# LH__MRF24_Module.net
KiCad netlist of a schematic drawn in EAGLE
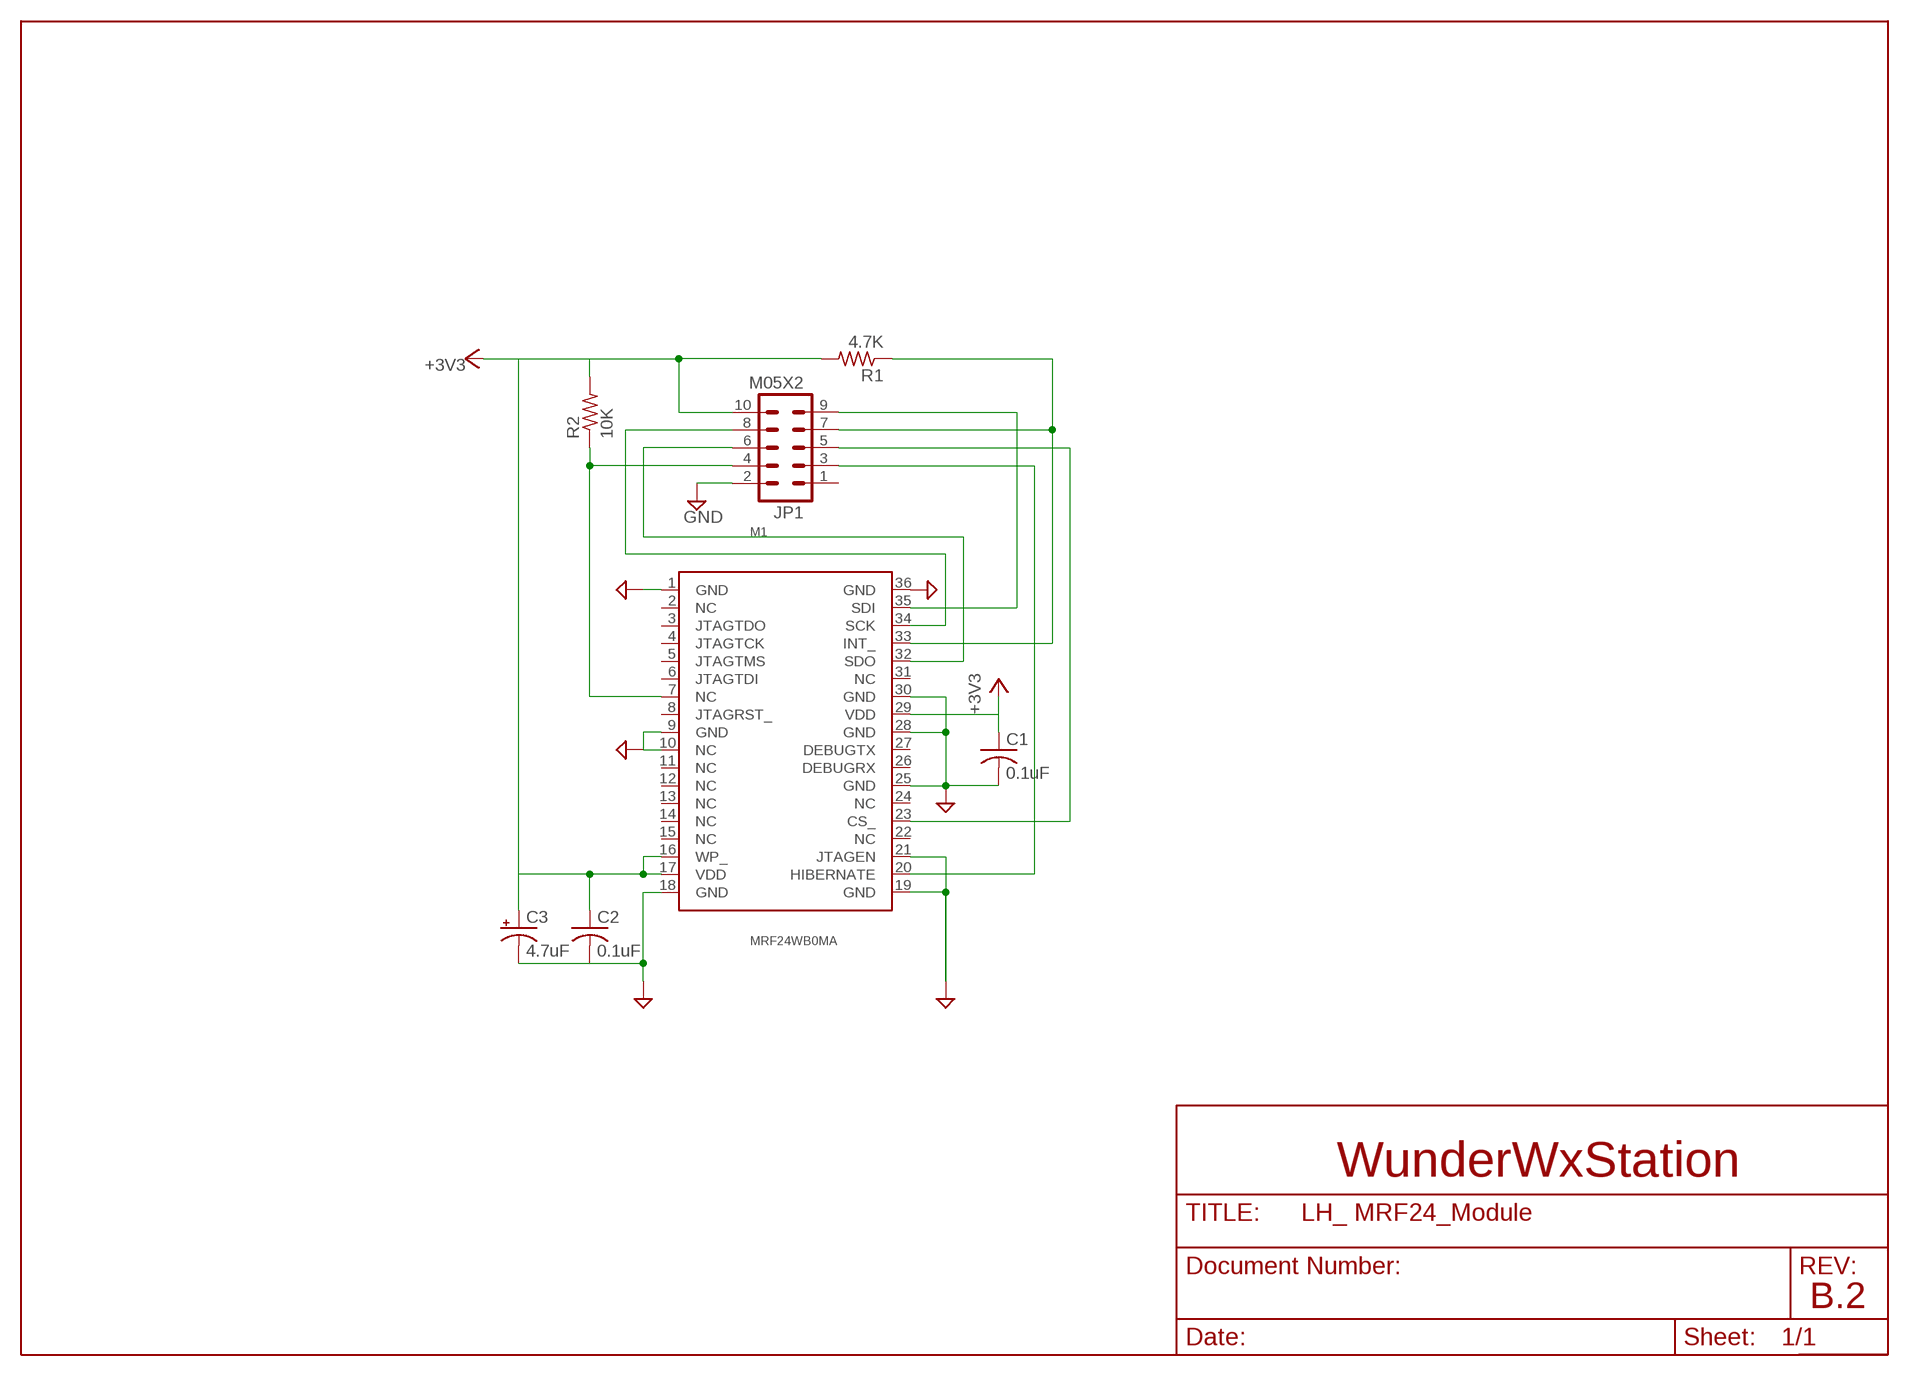
[diagram p0: schematic, sheet 1]

(export (version "E")
  (design (tool "Eeschema 10.0.6"))
  (components
    (comp (ref "C1")
      (value "0.1uF")
      (footprint "eagle-import:C0805")
      (libsource (lib "eagle-import") (part "C-USC0805"))
    )
    (comp (ref "C2")
      (value "0.1uF")
      (footprint "eagle-import:C0805")
      (libsource (lib "eagle-import") (part "C-USC0805"))
    )
    (comp (ref "C3")
      (value "4.7uF")
      (footprint "eagle-import:R_2012-12R")
      (libsource (lib "eagle-import") (part "CPOL-USR/2012-12R"))
    )
    (comp (ref "JP1")
      (value "M05X2")
      (footprint "eagle-import:2X5-RA-HEADER")
      (libsource (lib "eagle-import") (part "M05X2"))
    )
    (comp (ref "M1")
      (value "MRF24WB0MA")
      (footprint "eagle-import:MRF24W")
      (libsource (lib "eagle-import") (part "MR24WB0MA"))
    )
    (comp (ref "R1")
      (value "4.7K")
      (footprint "eagle-import:R0603")
      (libsource (lib "eagle-import") (part "R-US_R0603"))
    )
    (comp (ref "R2")
      (value "10K")
      (footprint "eagle-import:R0603")
      (libsource (lib "eagle-import") (part "R-US_R0603"))
    )
  )
  (nets
    (net (code "1") (name "+3V3") (class "Default")
      (node (ref "C1") (pin "1") (pinfunction "1_1") (pintype "passive"))
      (node (ref "C2") (pin "1") (pinfunction "1_1") (pintype "passive"))
      (node (ref "C3") (pin "+") (pinfunction "+_+") (pintype "passive"))
      (node (ref "JP1") (pin "10") (pinfunction "10_10") (pintype "passive"))
      (node (ref "M1") (pin "16") (pinfunction "WP__16") (pintype "bidirectional"))
      (node (ref "M1") (pin "17") (pinfunction "VDD_17") (pintype "bidirectional"))
      (node (ref "M1") (pin "29") (pinfunction "VDD_29") (pintype "bidirectional"))
      (node (ref "R1") (pin "2") (pinfunction "2_2") (pintype "passive"))
      (node (ref "R2") (pin "2") (pinfunction "2_2") (pintype "passive"))
    )
    (net (code "2") (name "GND") (class "Default")
      (node (ref "C1") (pin "2") (pinfunction "2_2") (pintype "passive"))
      (node (ref "C2") (pin "2") (pinfunction "2_2") (pintype "passive"))
      (node (ref "C3") (pin "-") (pinfunction "-_-") (pintype "passive"))
      (node (ref "JP1") (pin "2") (pinfunction "2_2") (pintype "passive"))
      (node (ref "M1") (pin "1") (pinfunction "GND_1") (pintype "bidirectional"))
      (node (ref "M1") (pin "10") (pinfunction "NC_10") (pintype "bidirectional"))
      (node (ref "M1") (pin "18") (pinfunction "GND_18") (pintype "bidirectional"))
      (node (ref "M1") (pin "19") (pinfunction "GND_19") (pintype "bidirectional"))
      (node (ref "M1") (pin "21") (pinfunction "JTAGEN_21") (pintype "bidirectional"))
      (node (ref "M1") (pin "25") (pinfunction "GND_25") (pintype "bidirectional"))
      (node (ref "M1") (pin "28") (pinfunction "GND_28") (pintype "bidirectional"))
      (node (ref "M1") (pin "30") (pinfunction "GND_30") (pintype "bidirectional"))
      (node (ref "M1") (pin "36") (pinfunction "GND_36") (pintype "bidirectional"))
      (node (ref "M1") (pin "9") (pinfunction "GND_9") (pintype "bidirectional"))
    )
    (net (code "3") (name "Net-(JP1-Pad4)") (class "Default")
      (node (ref "JP1") (pin "4") (pinfunction "4_4") (pintype "passive"))
      (node (ref "M1") (pin "7") (pinfunction "NC_7") (pintype "bidirectional"))
      (node (ref "R2") (pin "1") (pinfunction "1_1") (pintype "passive"))
    )
    (net (code "4") (name "Net-(M1-CS_)") (class "Default")
      (node (ref "JP1") (pin "5") (pinfunction "5_5") (pintype "passive"))
      (node (ref "M1") (pin "23") (pinfunction "CS__23") (pintype "bidirectional"))
    )
    (net (code "5") (name "Net-(M1-HIBERNATE)") (class "Default")
      (node (ref "JP1") (pin "3") (pinfunction "3_3") (pintype "passive"))
      (node (ref "M1") (pin "20") (pinfunction "HIBERNATE_20") (pintype "bidirectional"))
    )
    (net (code "6") (name "Net-(M1-INT_)") (class "Default")
      (node (ref "JP1") (pin "7") (pinfunction "7_7") (pintype "passive"))
      (node (ref "M1") (pin "33") (pinfunction "INT__33") (pintype "bidirectional"))
      (node (ref "R1") (pin "1") (pinfunction "1_1") (pintype "passive"))
    )
    (net (code "7") (name "Net-(M1-SCK)") (class "Default")
      (node (ref "JP1") (pin "8") (pinfunction "8_8") (pintype "passive"))
      (node (ref "M1") (pin "34") (pinfunction "SCK_34") (pintype "bidirectional"))
    )
    (net (code "8") (name "Net-(M1-SDI)") (class "Default")
      (node (ref "JP1") (pin "9") (pinfunction "9_9") (pintype "passive"))
      (node (ref "M1") (pin "35") (pinfunction "SDI_35") (pintype "bidirectional"))
    )
    (net (code "9") (name "Net-(M1-SDO)") (class "Default")
      (node (ref "JP1") (pin "6") (pinfunction "6_6") (pintype "passive"))
      (node (ref "M1") (pin "32") (pinfunction "SDO_32") (pintype "bidirectional"))
    )
    (net (code "10") (name "unconnected-(JP1-Pad1)") (class "Default")
      (node (ref "JP1") (pin "1") (pinfunction "1_1") (pintype "passive"))
    )
    (net (code "11") (name "unconnected-(M1-DEBUGRX-Pad26)") (class "Default")
      (node (ref "M1") (pin "26") (pinfunction "DEBUGRX_26") (pintype "bidirectional"))
    )
    (net (code "12") (name "unconnected-(M1-DEBUGTX-Pad27)") (class "Default")
      (node (ref "M1") (pin "27") (pinfunction "DEBUGTX_27") (pintype "bidirectional"))
    )
    (net (code "13") (name "unconnected-(M1-JTAGRST_-Pad8)") (class "Default")
      (node (ref "M1") (pin "8") (pinfunction "JTAGRST__8") (pintype "bidirectional"))
    )
    (net (code "14") (name "unconnected-(M1-JTAGTCK-Pad4)") (class "Default")
      (node (ref "M1") (pin "4") (pinfunction "JTAGTCK_4") (pintype "bidirectional"))
    )
    (net (code "15") (name "unconnected-(M1-JTAGTDI-Pad6)") (class "Default")
      (node (ref "M1") (pin "6") (pinfunction "JTAGTDI_6") (pintype "bidirectional"))
    )
    (net (code "16") (name "unconnected-(M1-JTAGTDO-Pad3)") (class "Default")
      (node (ref "M1") (pin "3") (pinfunction "JTAGTDO_3") (pintype "bidirectional"))
    )
    (net (code "17") (name "unconnected-(M1-JTAGTMS-Pad5)") (class "Default")
      (node (ref "M1") (pin "5") (pinfunction "JTAGTMS_5") (pintype "bidirectional"))
    )
    (net (code "18") (name "unconnected-(M1-NC-Pad2)") (class "Default")
      (node (ref "M1") (pin "2") (pinfunction "NC_2") (pintype "bidirectional"))
    )
    (net (code "19") (name "unconnected-(M1-NC-Pad11)") (class "Default")
      (node (ref "M1") (pin "11") (pinfunction "NC_11") (pintype "bidirectional"))
    )
    (net (code "20") (name "unconnected-(M1-NC-Pad12)") (class "Default")
      (node (ref "M1") (pin "12") (pinfunction "NC_12") (pintype "bidirectional"))
    )
    (net (code "21") (name "unconnected-(M1-NC-Pad13)") (class "Default")
      (node (ref "M1") (pin "13") (pinfunction "NC_13") (pintype "bidirectional"))
    )
    (net (code "22") (name "unconnected-(M1-NC-Pad14)") (class "Default")
      (node (ref "M1") (pin "14") (pinfunction "NC_14") (pintype "bidirectional"))
    )
    (net (code "23") (name "unconnected-(M1-NC-Pad15)") (class "Default")
      (node (ref "M1") (pin "15") (pinfunction "NC_15") (pintype "bidirectional"))
    )
    (net (code "24") (name "unconnected-(M1-NC-Pad22)") (class "Default")
      (node (ref "M1") (pin "22") (pinfunction "NC_22") (pintype "bidirectional"))
    )
    (net (code "25") (name "unconnected-(M1-NC-Pad24)") (class "Default")
      (node (ref "M1") (pin "24") (pinfunction "NC_24") (pintype "bidirectional"))
    )
    (net (code "26") (name "unconnected-(M1-NC-Pad31)") (class "Default")
      (node (ref "M1") (pin "31") (pinfunction "NC_31") (pintype "bidirectional"))
    )
  )
)
